# RS_485_V.net
KiCad netlist of a schematic drawn in Altium Designer
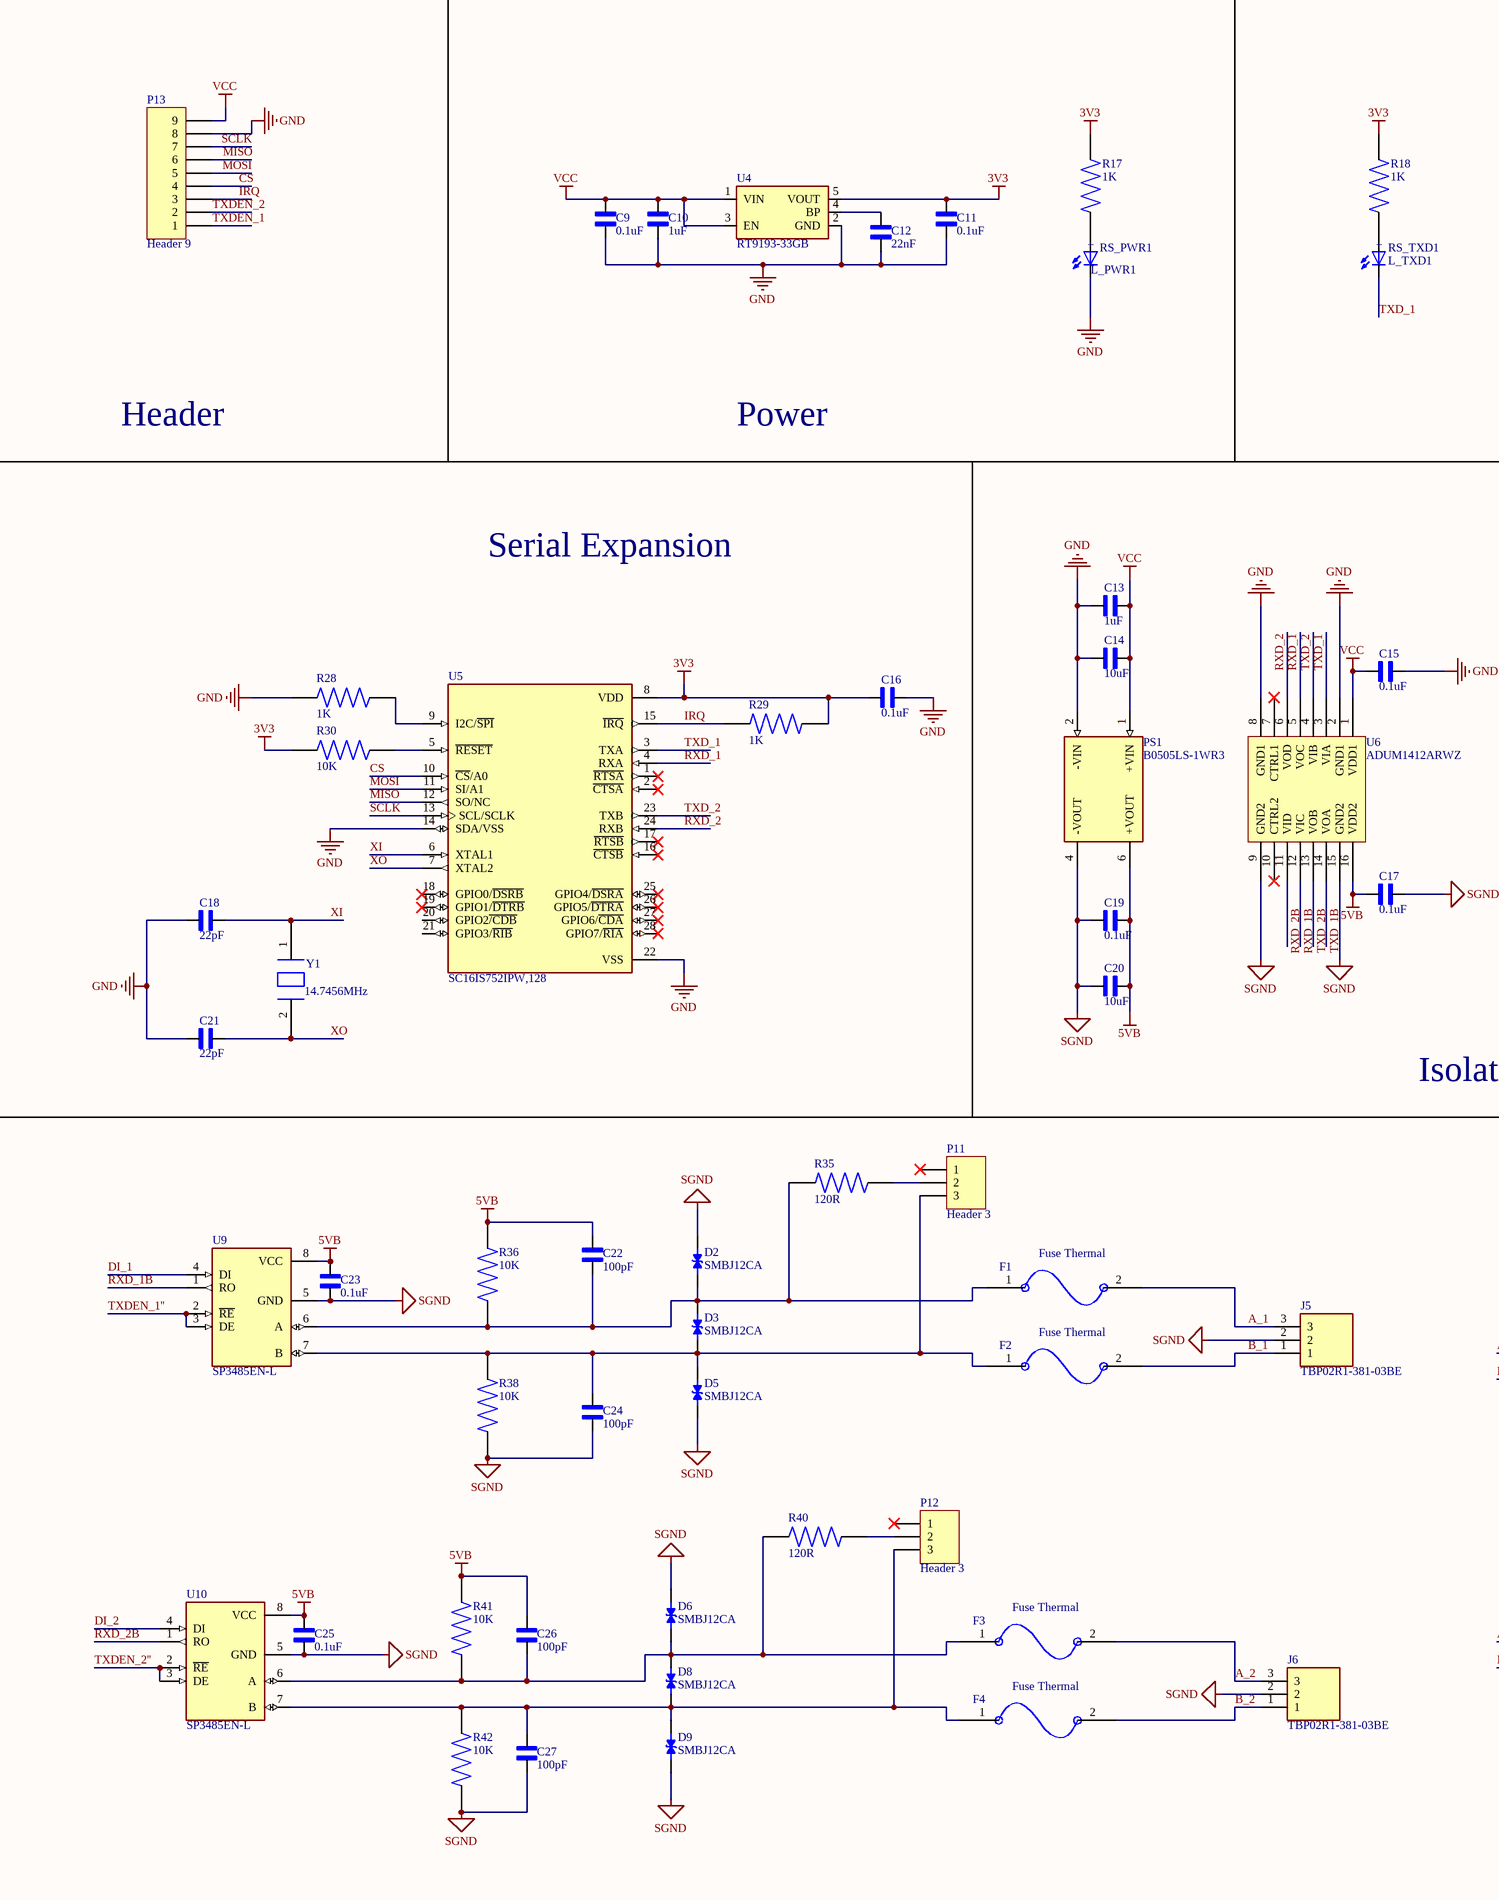
[diagram p0: RS_485_V.SchDoc, left]
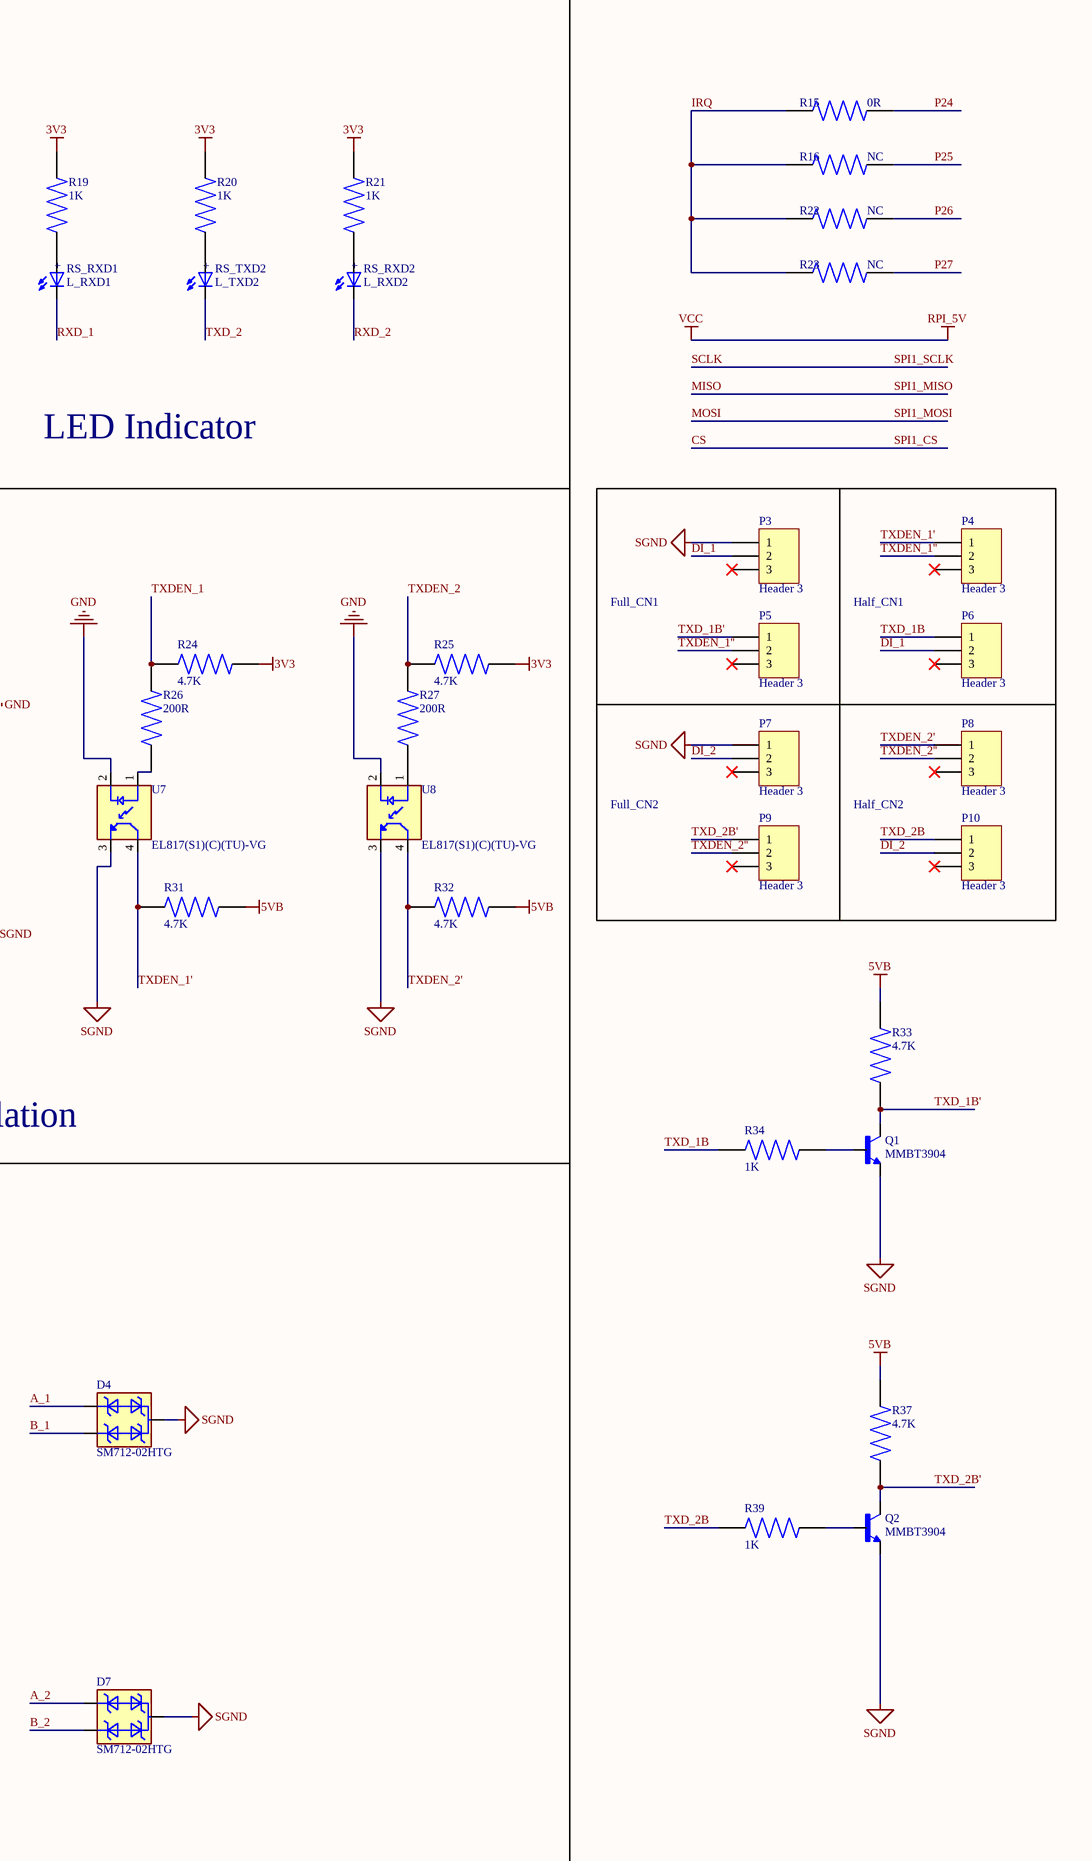
[diagram p1: RS_485_V.SchDoc, right]

(export (version "E")
  (design (tool "Eeschema 10.0.6"))
  (components
    (comp (ref "C9")
      (value "0.1uF")
      (footprint "CAPC1608X94N")
      (description "cap 0603 (1608 Metric)")
      (fields (field (name "MF") "Vishay Vitramon") (field (name "MP") "VJ0603D3R9DXCAP"))
      (libsource (lib "") (part "cap_0603_VJ0603D3R9DXCAP_2"))
    )
    (comp (ref "C10")
      (value "1uF")
      (footprint "CAPC1608X94N")
      (description "cap 0603 (1608 Metric)")
      (fields (field (name "MF") "Vishay Vitramon") (field (name "MP") "VJ0603D3R9DXCAP"))
      (libsource (lib "") (part "cap_0603_VJ0603D3R9DXCAP_2"))
    )
    (comp (ref "C11")
      (value "0.1uF")
      (footprint "CAPC1608X94N")
      (description "cap 0603 (1608 Metric)")
      (fields (field (name "MF") "Vishay Vitramon") (field (name "MP") "VJ0603D3R9DXCAP"))
      (libsource (lib "") (part "cap_0603_VJ0603D3R9DXCAP_2"))
    )
    (comp (ref "C12")
      (value "22nF")
      (footprint "CAPC1608X94N")
      (description "cap 0603 (1608 Metric)")
      (fields (field (name "MF") "Vishay Vitramon") (field (name "MP") "VJ0603D3R9DXCAP"))
      (libsource (lib "") (part "cap_0603_VJ0603D3R9DXCAP_2"))
    )
    (comp (ref "C13")
      (value "1uF")
      (footprint "CAPC1608X94N")
      (description "cap 0603 (1608 Metric)")
      (fields (field (name "MF") "Vishay Vitramon") (field (name "MP") "VJ0603D3R9DXCAP"))
      (libsource (lib "") (part "cap_0603_VJ0603D3R9DXCAP_1"))
    )
    (comp (ref "C14")
      (value "10uF")
      (footprint "CAPC1608X94N")
      (description "cap 0603 (1608 Metric)")
      (fields (field (name "MF") "Vishay Vitramon") (field (name "MP") "VJ0603D3R9DXCAP"))
      (libsource (lib "") (part "cap_0603_VJ0603D3R9DXCAP_1"))
    )
    (comp (ref "C15")
      (value "0.1uF")
      (footprint "CAPC1608X94N")
      (description "cap 0603 (1608 Metric)")
      (fields (field (name "MF") "Vishay Vitramon") (field (name "MP") "VJ0603D3R9DXCAP"))
      (libsource (lib "") (part "cap_0603_VJ0603D3R9DXCAP_1"))
    )
    (comp (ref "C16")
      (value "0.1uF")
      (footprint "CAPC1608X94N")
      (description "cap 0603 (1608 Metric)")
      (fields (field (name "MF") "Vishay Vitramon") (field (name "MP") "VJ0603D3R9DXCAP"))
      (libsource (lib "") (part "cap_0603_VJ0603D3R9DXCAP_1"))
    )
    (comp (ref "C17")
      (value "0.1uF")
      (footprint "CAPC1608X94N")
      (description "cap 0603 (1608 Metric)")
      (fields (field (name "MF") "Vishay Vitramon") (field (name "MP") "VJ0603D3R9DXCAP"))
      (libsource (lib "") (part "cap_0603_VJ0603D3R9DXCAP_1"))
    )
    (comp (ref "C18")
      (value "22pF")
      (footprint "CAPC1608X94N")
      (description "cap 0603 (1608 Metric)")
      (fields (field (name "MF") "Vishay Vitramon") (field (name "MP") "VJ0603D3R9DXCAP"))
      (libsource (lib "") (part "cap_0603_VJ0603D3R9DXCAP_1"))
    )
    (comp (ref "C19")
      (value "0.1uF")
      (footprint "CAPC1608X94N")
      (description "cap 0603 (1608 Metric)")
      (fields (field (name "MF") "Vishay Vitramon") (field (name "MP") "VJ0603D3R9DXCAP"))
      (libsource (lib "") (part "cap_0603_VJ0603D3R9DXCAP_1"))
    )
    (comp (ref "C20")
      (value "10uF")
      (footprint "CAPC1608X94N")
      (description "cap 0603 (1608 Metric)")
      (fields (field (name "MF") "Vishay Vitramon") (field (name "MP") "VJ0603D3R9DXCAP"))
      (libsource (lib "") (part "cap_0603_VJ0603D3R9DXCAP_1"))
    )
    (comp (ref "C21")
      (value "22pF")
      (footprint "CAPC1608X94N")
      (description "cap 0603 (1608 Metric)")
      (fields (field (name "MF") "Vishay Vitramon") (field (name "MP") "VJ0603D3R9DXCAP"))
      (libsource (lib "") (part "cap_0603_VJ0603D3R9DXCAP_1"))
    )
    (comp (ref "C22")
      (value "100pF")
      (footprint "CAPC1608X94N")
      (description "cap 0603 (1608 Metric)")
      (fields (field (name "MF") "Vishay Vitramon") (field (name "MP") "VJ0603D3R9DXCAP"))
      (libsource (lib "VIETTIEN") (part "cap_0603_VJ0603D3R9DXCAP"))
    )
    (comp (ref "C23")
      (value "0.1uF")
      (footprint "CAPC1608X94N")
      (description "cap 0603 (1608 Metric)")
      (fields (field (name "MF") "Vishay Vitramon") (field (name "MP") "VJ0603D3R9DXCAP"))
      (libsource (lib "VIETTIEN") (part "cap_0603_VJ0603D3R9DXCAP"))
    )
    (comp (ref "C24")
      (value "100pF")
      (footprint "CAPC1608X94N")
      (description "cap 0603 (1608 Metric)")
      (fields (field (name "MF") "Vishay Vitramon") (field (name "MP") "VJ0603D3R9DXCAP"))
      (libsource (lib "VIETTIEN") (part "cap_0603_VJ0603D3R9DXCAP"))
    )
    (comp (ref "C25")
      (value "0.1uF")
      (footprint "CAPC1608X94N")
      (description "cap 0603 (1608 Metric)")
      (fields (field (name "MF") "Vishay Vitramon") (field (name "MP") "VJ0603D3R9DXCAP"))
      (libsource (lib "VIETTIEN") (part "cap_0603_VJ0603D3R9DXCAP"))
    )
    (comp (ref "C26")
      (value "100pF")
      (footprint "CAPC1608X94N")
      (description "cap 0603 (1608 Metric)")
      (fields (field (name "MF") "Vishay Vitramon") (field (name "MP") "VJ0603D3R9DXCAP"))
      (libsource (lib "VIETTIEN") (part "cap_0603_VJ0603D3R9DXCAP"))
    )
    (comp (ref "C27")
      (value "100pF")
      (footprint "CAPC1608X94N")
      (description "cap 0603 (1608 Metric)")
      (fields (field (name "MF") "Vishay Vitramon") (field (name "MP") "VJ0603D3R9DXCAP"))
      (libsource (lib "VIETTIEN") (part "cap_0603_VJ0603D3R9DXCAP"))
    )
    (comp (ref "D2")
      (value "SMBJ12CA")
      (footprint "DIOM4336X265N")
      (fields
        (field (name "MF") "{'manufacturer': u'Diodes Incorporated'}")
        (field (name "MP") "SMBJ10CA-13-F")
      )
      (libsource (lib "VIETTIEN") (part "SMBJ10CA-13-F"))
    )
    (comp (ref "D3")
      (value "SMBJ12CA")
      (footprint "DIOM4336X265N")
      (fields
        (field (name "MF") "{'manufacturer': u'Diodes Incorporated'}")
        (field (name "MP") "SMBJ10CA-13-F")
      )
      (libsource (lib "VIETTIEN") (part "SMBJ10CA-13-F"))
    )
    (comp (ref "D4")
      (value "SM712-02HTG")
      (footprint "SOT23")
      (fields (field (name "MF") "Littelfuse Inc."))
      (libsource (lib "VIETTIEN") (part "SM712-02HTG"))
    )
    (comp (ref "D5")
      (value "SMBJ12CA")
      (footprint "DIOM4336X265N")
      (fields
        (field (name "MF") "{'manufacturer': u'Diodes Incorporated'}")
        (field (name "MP") "SMBJ10CA-13-F")
      )
      (libsource (lib "VIETTIEN") (part "SMBJ10CA-13-F"))
    )
    (comp (ref "D6")
      (value "SMBJ12CA")
      (footprint "DIOM4336X265N")
      (fields
        (field (name "MF") "{'manufacturer': u'Diodes Incorporated'}")
        (field (name "MP") "SMBJ10CA-13-F")
      )
      (libsource (lib "VIETTIEN") (part "SMBJ10CA-13-F"))
    )
    (comp (ref "D7")
      (value "SM712-02HTG")
      (footprint "SOT23")
      (fields (field (name "MF") "Littelfuse Inc."))
      (libsource (lib "VIETTIEN") (part "SM712-02HTG"))
    )
    (comp (ref "D8")
      (value "SMBJ12CA")
      (footprint "DIOM4336X265N")
      (fields
        (field (name "MF") "{'manufacturer': u'Diodes Incorporated'}")
        (field (name "MP") "SMBJ10CA-13-F")
      )
      (libsource (lib "VIETTIEN") (part "SMBJ10CA-13-F"))
    )
    (comp (ref "D9")
      (value "SMBJ12CA")
      (footprint "DIOM4336X265N")
      (fields
        (field (name "MF") "{'manufacturer': u'Diodes Incorporated'}")
        (field (name "MP") "SMBJ10CA-13-F")
      )
      (libsource (lib "VIETTIEN") (part "SMBJ10CA-13-F"))
    )
    (comp (ref "F1")
      (value "Fuse Thermal")
      (footprint "Fuse_thermal")
      (libsource (lib "VIETTIEN") (part "Fuse Thermal"))
    )
    (comp (ref "F2")
      (value "Fuse Thermal")
      (footprint "Fuse_thermal")
      (libsource (lib "VIETTIEN") (part "Fuse Thermal"))
    )
    (comp (ref "F3")
      (value "Fuse Thermal")
      (footprint "Fuse_thermal")
      (libsource (lib "VIETTIEN") (part "Fuse Thermal"))
    )
    (comp (ref "F4")
      (value "Fuse Thermal")
      (footprint "Fuse_thermal")
      (libsource (lib "VIETTIEN") (part "Fuse Thermal"))
    )
    (comp (ref "J5")
      (value "TBP02R1-381-03BE")
      (footprint "CUI_TBP02R1-381-03BE")
      (description "2~24 Poles, Pluggable,Receptacle, Horizontal, 3.81 Pitch, Terminal Block Connector")
      (fields (field (name "MF") "Same Sky"))
      (libsource (lib "VIETTIEN") (part "TBP02R1-381-03BE"))
    )
    (comp (ref "J6")
      (value "TBP02R1-381-03BE")
      (footprint "CUI_TBP02R1-381-03BE")
      (description "2~24 Poles, Pluggable,Receptacle, Horizontal, 3.81 Pitch, Terminal Block Connector")
      (fields (field (name "MF") "Same Sky"))
      (libsource (lib "VIETTIEN") (part "TBP02R1-381-03BE"))
    )
    (comp (ref "P3")
      (value "Header 3")
      (footprint "HDR1X3")
      (description "Header, 3-Pin")
      (fields (field (name "PUBLISHER") "Altium Limited"))
      (libsource (lib "Miscellaneous Connectors") (part "Header 3"))
    )
    (comp (ref "P4")
      (value "Header 3")
      (footprint "HDR1X3")
      (description "Header, 3-Pin")
      (fields (field (name "PUBLISHER") "Altium Limited"))
      (libsource (lib "Miscellaneous Connectors") (part "Header 3"))
    )
    (comp (ref "P5")
      (value "Header 3")
      (footprint "HDR1X3")
      (description "Header, 3-Pin")
      (fields (field (name "PUBLISHER") "Altium Limited"))
      (libsource (lib "Miscellaneous Connectors") (part "Header 3"))
    )
    (comp (ref "P6")
      (value "Header 3")
      (footprint "HDR1X3")
      (description "Header, 3-Pin")
      (fields (field (name "PUBLISHER") "Altium Limited"))
      (libsource (lib "Miscellaneous Connectors") (part "Header 3"))
    )
    (comp (ref "P7")
      (value "Header 3")
      (footprint "HDR1X3")
      (description "Header, 3-Pin")
      (fields (field (name "PUBLISHER") "Altium Limited"))
      (libsource (lib "Miscellaneous Connectors") (part "Header 3"))
    )
    (comp (ref "P8")
      (value "Header 3")
      (footprint "HDR1X3")
      (description "Header, 3-Pin")
      (fields (field (name "PUBLISHER") "Altium Limited"))
      (libsource (lib "Miscellaneous Connectors") (part "Header 3"))
    )
    (comp (ref "P9")
      (value "Header 3")
      (footprint "HDR1X3")
      (description "Header, 3-Pin")
      (fields (field (name "PUBLISHER") "Altium Limited"))
      (libsource (lib "Miscellaneous Connectors") (part "Header 3"))
    )
    (comp (ref "P10")
      (value "Header 3")
      (footprint "HDR1X3")
      (description "Header, 3-Pin")
      (fields (field (name "PUBLISHER") "Altium Limited"))
      (libsource (lib "Miscellaneous Connectors") (part "Header 3"))
    )
    (comp (ref "P11")
      (value "Header 3")
      (footprint "HDR1X3")
      (description "Header, 3-Pin")
      (fields (field (name "PUBLISHER") "Altium Limited"))
      (libsource (lib "Miscellaneous Connectors") (part "Header 3"))
    )
    (comp (ref "P12")
      (value "Header 3")
      (footprint "HDR1X3")
      (description "Header, 3-Pin")
      (fields (field (name "PUBLISHER") "Altium Limited"))
      (libsource (lib "Miscellaneous Connectors") (part "Header 3"))
    )
    (comp (ref "P13")
      (value "Header 9")
      (footprint "HDR1X9")
      (description "Header, 9-Pin")
      (fields (field (name "PUBLISHER") "Altium Limited"))
      (libsource (lib "Miscellaneous Connectors") (part "Header 9"))
    )
    (comp (ref "PS1")
      (value "B0505LS-1WR3")
      (footprint "CONV_RFB-0505S")
      (description "1W DC/DC-Converter 'ECONOLINE' SIP7 1kV unreg")
      (fields (field (name "MF") "Recom Power") (field (name "MP") "RFB-0505S"))
      (libsource (lib "VIETTIEN") (part "B0505LS-1WR3"))
    )
    (comp (ref "Q1")
      (value "MMBT3904")
      (footprint "TRANS_MMBT3904")
      (description "BJT, SOT-23, 40V, 200mA, NPN, 0.35W, 150Â°C")
      (fields (field (name "MF") "Diotec Semiconductor"))
      (libsource (lib "VIETTIEN") (part "MMBT3904"))
    )
    (comp (ref "Q2")
      (value "MMBT3904")
      (footprint "TRANS_MMBT3904")
      (description "BJT, SOT-23, 40V, 200mA, NPN, 0.35W, 150Â°C")
      (fields (field (name "MF") "Diotec Semiconductor"))
      (libsource (lib "VIETTIEN") (part "MMBT3904"))
    )
    (comp (ref "R15")
      (value "0R")
      (footprint "RES_ERJU03J474V")
      (description "0603 Anti-Sulfurated")
      (fields (field (name "MF") "Panasonic") (field (name "MP") "ERJU03J474V"))
      (libsource (lib "VIETTIEN") (part "res_0603_ERJU03J474V"))
    )
    (comp (ref "R16")
      (value "NC")
      (footprint "RES_ERJU03J474V")
      (description "0603 Anti-Sulfurated")
      (fields (field (name "MF") "Panasonic") (field (name "MP") "ERJU03J474V"))
      (libsource (lib "VIETTIEN") (part "res_0603_ERJU03J474V"))
    )
    (comp (ref "R17")
      (value "1K")
      (footprint "RES_ERJU03J474V")
      (description "0603 Anti-Sulfurated")
      (fields (field (name "MF") "Panasonic") (field (name "MP") "ERJU03J474V"))
      (libsource (lib "VIETTIEN") (part "res_0603_ERJU03J474V"))
    )
    (comp (ref "R18")
      (value "1K")
      (footprint "RES_ERJU03J474V")
      (description "0603 Anti-Sulfurated")
      (fields (field (name "MF") "Panasonic") (field (name "MP") "ERJU03J474V"))
      (libsource (lib "VIETTIEN") (part "res_0603_ERJU03J474V"))
    )
    (comp (ref "R19")
      (value "1K")
      (footprint "RES_ERJU03J474V")
      (description "0603 Anti-Sulfurated")
      (fields (field (name "MF") "Panasonic") (field (name "MP") "ERJU03J474V"))
      (libsource (lib "VIETTIEN") (part "res_0603_ERJU03J474V"))
    )
    (comp (ref "R20")
      (value "1K")
      (footprint "RES_ERJU03J474V")
      (description "0603 Anti-Sulfurated")
      (fields (field (name "MF") "Panasonic") (field (name "MP") "ERJU03J474V"))
      (libsource (lib "VIETTIEN") (part "res_0603_ERJU03J474V"))
    )
    (comp (ref "R21")
      (value "1K")
      (footprint "RES_ERJU03J474V")
      (description "0603 Anti-Sulfurated")
      (fields (field (name "MF") "Panasonic") (field (name "MP") "ERJU03J474V"))
      (libsource (lib "VIETTIEN") (part "res_0603_ERJU03J474V"))
    )
    (comp (ref "R22")
      (value "NC")
      (footprint "RES_ERJU03J474V")
      (description "0603 Anti-Sulfurated")
      (fields (field (name "MF") "Panasonic") (field (name "MP") "ERJU03J474V"))
      (libsource (lib "VIETTIEN") (part "res_0603_ERJU03J474V"))
    )
    (comp (ref "R23")
      (value "NC")
      (footprint "RES_ERJU03J474V")
      (description "0603 Anti-Sulfurated")
      (fields (field (name "MF") "Panasonic") (field (name "MP") "ERJU03J474V"))
      (libsource (lib "VIETTIEN") (part "res_0603_ERJU03J474V"))
    )
    (comp (ref "R24")
      (value "4.7K")
      (footprint "RES_ERJU03J474V")
      (description "0603 Anti-Sulfurated")
      (fields (field (name "MF") "Panasonic") (field (name "MP") "ERJU03J474V"))
      (libsource (lib "VIETTIEN") (part "res_0603_ERJU03J474V"))
    )
    (comp (ref "R25")
      (value "4.7K")
      (footprint "RES_ERJU03J474V")
      (description "0603 Anti-Sulfurated")
      (fields (field (name "MF") "Panasonic") (field (name "MP") "ERJU03J474V"))
      (libsource (lib "VIETTIEN") (part "res_0603_ERJU03J474V"))
    )
    (comp (ref "R26")
      (value "200R")
      (footprint "RES_ERJU03J474V")
      (description "0603 Anti-Sulfurated")
      (fields (field (name "MF") "Panasonic") (field (name "MP") "ERJU03J474V"))
      (libsource (lib "VIETTIEN") (part "res_0603_ERJU03J474V"))
    )
    (comp (ref "R27")
      (value "200R")
      (footprint "RES_ERJU03J474V")
      (description "0603 Anti-Sulfurated")
      (fields (field (name "MF") "Panasonic") (field (name "MP") "ERJU03J474V"))
      (libsource (lib "VIETTIEN") (part "res_0603_ERJU03J474V"))
    )
    (comp (ref "R28")
      (value "1K")
      (footprint "RES_ERJU03J474V")
      (description "0603 Anti-Sulfurated")
      (fields (field (name "MF") "Panasonic") (field (name "MP") "ERJU03J474V"))
      (libsource (lib "VIETTIEN") (part "res_0603_ERJU03J474V"))
    )
    (comp (ref "R29")
      (value "1K")
      (footprint "RES_ERJU03J474V")
      (description "0603 Anti-Sulfurated")
      (fields (field (name "MF") "Panasonic") (field (name "MP") "ERJU03J474V"))
      (libsource (lib "VIETTIEN") (part "res_0603_ERJU03J474V"))
    )
    (comp (ref "R30")
      (value "10K")
      (footprint "RES_ERJU03J474V")
      (description "0603 Anti-Sulfurated")
      (fields (field (name "MF") "Panasonic") (field (name "MP") "ERJU03J474V"))
      (libsource (lib "VIETTIEN") (part "res_0603_ERJU03J474V"))
    )
    (comp (ref "R31")
      (value "4.7K")
      (footprint "RES_ERJU03J474V")
      (description "0603 Anti-Sulfurated")
      (fields (field (name "MF") "Panasonic") (field (name "MP") "ERJU03J474V"))
      (libsource (lib "VIETTIEN") (part "res_0603_ERJU03J474V"))
    )
    (comp (ref "R32")
      (value "4.7K")
      (footprint "RES_ERJU03J474V")
      (description "0603 Anti-Sulfurated")
      (fields (field (name "MF") "Panasonic") (field (name "MP") "ERJU03J474V"))
      (libsource (lib "VIETTIEN") (part "res_0603_ERJU03J474V"))
    )
    (comp (ref "R33")
      (value "4.7K")
      (footprint "RES_ERJU03J474V")
      (description "0603 Anti-Sulfurated")
      (fields (field (name "MF") "Panasonic") (field (name "MP") "ERJU03J474V"))
      (libsource (lib "VIETTIEN") (part "res_0603_ERJU03J474V"))
    )
    (comp (ref "R34")
      (value "1K")
      (footprint "RES_ERJU03J474V")
      (description "0603 Anti-Sulfurated")
      (fields (field (name "MF") "Panasonic") (field (name "MP") "ERJU03J474V"))
      (libsource (lib "VIETTIEN") (part "res_0603_ERJU03J474V"))
    )
    (comp (ref "R35")
      (value "120R")
      (footprint "RES_ERJU03J474V")
      (description "0603 Anti-Sulfurated")
      (fields (field (name "MF") "Panasonic") (field (name "MP") "ERJU03J474V"))
      (libsource (lib "VIETTIEN") (part "res_0603_ERJU03J474V"))
    )
    (comp (ref "R36")
      (value "10K")
      (footprint "RES_ERJU03J474V")
      (description "0603 Anti-Sulfurated")
      (fields (field (name "MF") "Panasonic") (field (name "MP") "ERJU03J474V"))
      (libsource (lib "VIETTIEN") (part "res_0603_ERJU03J474V"))
    )
    (comp (ref "R37")
      (value "4.7K")
      (footprint "RES_ERJU03J474V")
      (description "0603 Anti-Sulfurated")
      (fields (field (name "MF") "Panasonic") (field (name "MP") "ERJU03J474V"))
      (libsource (lib "VIETTIEN") (part "res_0603_ERJU03J474V"))
    )
    (comp (ref "R38")
      (value "10K")
      (footprint "RES_ERJU03J474V")
      (description "0603 Anti-Sulfurated")
      (fields (field (name "MF") "Panasonic") (field (name "MP") "ERJU03J474V"))
      (libsource (lib "VIETTIEN") (part "res_0603_ERJU03J474V"))
    )
    (comp (ref "R39")
      (value "1K")
      (footprint "RES_ERJU03J474V")
      (description "0603 Anti-Sulfurated")
      (fields (field (name "MF") "Panasonic") (field (name "MP") "ERJU03J474V"))
      (libsource (lib "VIETTIEN") (part "res_0603_ERJU03J474V"))
    )
    (comp (ref "R40")
      (value "120R")
      (footprint "RES_ERJU03J474V")
      (description "0603 Anti-Sulfurated")
      (fields (field (name "MF") "Panasonic") (field (name "MP") "ERJU03J474V"))
      (libsource (lib "VIETTIEN") (part "res_0603_ERJU03J474V"))
    )
    (comp (ref "R41")
      (value "10K")
      (footprint "RES_ERJU03J474V")
      (description "0603 Anti-Sulfurated")
      (fields (field (name "MF") "Panasonic") (field (name "MP") "ERJU03J474V"))
      (libsource (lib "VIETTIEN") (part "res_0603_ERJU03J474V"))
    )
    (comp (ref "R42")
      (value "10K")
      (footprint "RES_ERJU03J474V")
      (description "0603 Anti-Sulfurated")
      (fields (field (name "MF") "Panasonic") (field (name "MP") "ERJU03J474V"))
      (libsource (lib "VIETTIEN") (part "res_0603_ERJU03J474V"))
    )
    (comp (ref "RS_PWR1")
      (value "L_PWR1")
      (footprint "WL-SMCW_1206")
      (description "1206, Blue Typ.(@20mA): 470nm, 145mcd, 3.2V, 140Â° InGaN")
      (fields (field (name "MF") "Wurth Electronics") (field (name "MP") "150120BS75000"))
      (libsource (lib "VIETTIEN") (part "WL-SMCW_1206"))
    )
    (comp (ref "RS_RXD1")
      (value "L_RXD1")
      (footprint "WL-SMCW_1206")
      (description "1206, Blue Typ.(@20mA): 470nm, 145mcd, 3.2V, 140Â° InGaN")
      (fields (field (name "MF") "Wurth Electronics") (field (name "MP") "150120BS75000"))
      (libsource (lib "VIETTIEN") (part "WL-SMCW_1206"))
    )
    (comp (ref "RS_RXD2")
      (value "L_RXD2")
      (footprint "WL-SMCW_1206")
      (description "1206, Blue Typ.(@20mA): 470nm, 145mcd, 3.2V, 140Â° InGaN")
      (fields (field (name "MF") "Wurth Electronics") (field (name "MP") "150120BS75000"))
      (libsource (lib "VIETTIEN") (part "WL-SMCW_1206"))
    )
    (comp (ref "RS_TXD1")
      (value "L_TXD1")
      (footprint "WL-SMCW_1206")
      (description "1206, Blue Typ.(@20mA): 470nm, 145mcd, 3.2V, 140Â° InGaN")
      (fields (field (name "MF") "Wurth Electronics") (field (name "MP") "150120BS75000"))
      (libsource (lib "VIETTIEN") (part "WL-SMCW_1206"))
    )
    (comp (ref "RS_TXD2")
      (value "L_TXD2")
      (footprint "WL-SMCW_1206")
      (description "1206, Blue Typ.(@20mA): 470nm, 145mcd, 3.2V, 140Â° InGaN")
      (fields (field (name "MF") "Wurth Electronics") (field (name "MP") "150120BS75000"))
      (libsource (lib "VIETTIEN") (part "WL-SMCW_1206"))
    )
    (comp (ref "U4")
      (value "RT9193-33GB")
      (footprint "SOT23-5_TEXAS_INSTRUMETNS")
      (description "Linear Voltage Regulator IC Positive Fixed 1 Output  300mA SOT-23-5")
      (fields (field (name "MF") "Richtek Technology Corp") (field (name "MP") "RT919333GB"))
      (libsource (lib "VIETTIEN") (part "RT9193-33GB"))
    )
    (comp (ref "U5")
      (value "SC16IS752IPW,128")
      (footprint "SOP65P640X110-28N")
      (description "RS232, RS485 Controller - IÂ²C, SPI, UART Interface 28-TSSOP")
      (fields (field (name "MF") "NXP Semiconductors"))
      (libsource (lib "VIETTIEN") (part "SC16IS752IPW,128"))
    )
    (comp (ref "U6")
      (value "ADUM1412ARWZ")
      (footprint "SOIC127P1032X265-16N")
      (description "Quad-Channel Digital Isolator")
      (libsource (lib "VIETTIEN") (part "ADUM1412ARWZ"))
    )
    (comp (ref "U7")
      (value "EL817(S1)(C)(TU)-VG")
      (footprint "SOIC254P1030X390-4N_EL817(S1)(C)(TU)-VG")
      (description "Optoisolator Transistor Output 5000Vrms 1 Channel 4-SMD")
      (fields (field (name "MF") "Everlight Electronics") (field (name "MP") "EL817(S1)(A)(TU)-VG"))
      (libsource (lib "VIETTIEN") (part "EL817(S1)(C)(TU)-VG"))
    )
    (comp (ref "U8")
      (value "EL817(S1)(C)(TU)-VG")
      (footprint "SOIC254P1030X390-4N_EL817(S1)(C)(TU)-VG")
      (description "Optoisolator Transistor Output 5000Vrms 1 Channel 4-SMD")
      (fields (field (name "MF") "Everlight Electronics") (field (name "MP") "EL817(S1)(A)(TU)-VG"))
      (libsource (lib "VIETTIEN") (part "EL817(S1)(C)(TU)-VG"))
    )
    (comp (ref "U9")
      (value "SP3485EN-L")
      (footprint "SOIC127P599X175-8N")
      (description "1/1 Transceiver Half RS422, RS485 8-SOIC")
      (fields (field (name "MF") "MaxLinear, Inc."))
      (libsource (lib "VIETTIEN") (part "SP3485EN-L"))
    )
    (comp (ref "U10")
      (value "SP3485EN-L")
      (footprint "SOIC127P599X175-8N")
      (description "1/1 Transceiver Half RS422, RS485 8-SOIC")
      (fields (field (name "MF") "MaxLinear, Inc."))
      (libsource (lib "VIETTIEN") (part "SP3485EN-L"))
    )
    (comp (ref "Y1")
      (value "14.7456MHz")
      (footprint "CRY_HC_49_S")
      (description "Crystal For all Crystal 2pin.")
      (libsource (lib "VIETTIEN") (part "Thach anh"))
    )
  )
  (nets
    (net (code "1") (name "/A_1") (class "Default")
      (node (ref "D4") (pin "1") (pinfunction "1_1") (pintype "passive"))
      (node (ref "F1") (pin "2") (pintype "passive"))
      (node (ref "J5") (pin "3") (pinfunction "3_3") (pintype "passive"))
    )
    (net (code "2") (name "/A_2") (class "Default")
      (node (ref "D7") (pin "1") (pinfunction "1_1") (pintype "passive"))
      (node (ref "F3") (pin "2") (pintype "passive"))
      (node (ref "J6") (pin "3") (pinfunction "3_3") (pintype "passive"))
    )
    (net (code "3") (name "/B_1") (class "Default")
      (node (ref "D4") (pin "2") (pinfunction "2_2") (pintype "passive"))
      (node (ref "F2") (pin "2") (pintype "passive"))
      (node (ref "J5") (pin "1") (pinfunction "1_1") (pintype "passive"))
    )
    (net (code "4") (name "/B_2") (class "Default")
      (node (ref "D7") (pin "2") (pinfunction "2_2") (pintype "passive"))
      (node (ref "F4") (pin "2") (pintype "passive"))
      (node (ref "J6") (pin "1") (pinfunction "1_1") (pintype "passive"))
    )
    (net (code "5") (name "/CS") (class "Default")
      (node (ref "P13") (pin "4") (pinfunction "4_4") (pintype "passive"))
      (node (ref "U5") (pin "10") (pinfunction "~{CS}/A0_10") (pintype "input"))
    )
    (net (code "6") (name "/DI_1") (class "Default")
      (node (ref "P3") (pin "2") (pinfunction "2_2") (pintype "passive"))
      (node (ref "P6") (pin "2") (pinfunction "2_2") (pintype "passive"))
      (node (ref "U9") (pin "4") (pinfunction "DI_4") (pintype "input"))
    )
    (net (code "7") (name "/DI_2") (class "Default")
      (node (ref "P10") (pin "2") (pinfunction "2_2") (pintype "passive"))
      (node (ref "P7") (pin "2") (pinfunction "2_2") (pintype "passive"))
      (node (ref "U10") (pin "4") (pinfunction "DI_4") (pintype "input"))
    )
    (net (code "8") (name "/IRQ") (class "Default")
      (node (ref "P13") (pin "3") (pinfunction "3_3") (pintype "passive"))
      (node (ref "R15") (pin "1") (pinfunction "1_1") (pintype "passive"))
      (node (ref "R16") (pin "1") (pinfunction "1_1") (pintype "passive"))
      (node (ref "R22") (pin "1") (pinfunction "1_1") (pintype "passive"))
      (node (ref "R23") (pin "1") (pinfunction "1_1") (pintype "passive"))
      (node (ref "R29") (pin "1") (pinfunction "1_1") (pintype "passive"))
      (node (ref "U5") (pin "15") (pinfunction "~{IRQ}_15") (pintype "output"))
    )
    (net (code "9") (name "/MISO") (class "Default")
      (node (ref "P13") (pin "6") (pinfunction "6_6") (pintype "passive"))
      (node (ref "U5") (pin "12") (pinfunction "SO/NC_12") (pintype "output"))
    )
    (net (code "10") (name "/MOSI") (class "Default")
      (node (ref "P13") (pin "5") (pinfunction "5_5") (pintype "passive"))
      (node (ref "U5") (pin "11") (pinfunction "SI/A1_11") (pintype "input"))
    )
    (net (code "11") (name "/P24") (class "Default")
      (node (ref "R15") (pin "2") (pinfunction "2_2") (pintype "passive"))
    )
    (net (code "12") (name "/P25") (class "Default")
      (node (ref "R16") (pin "2") (pinfunction "2_2") (pintype "passive"))
    )
    (net (code "13") (name "/P26") (class "Default")
      (node (ref "R22") (pin "2") (pinfunction "2_2") (pintype "passive"))
    )
    (net (code "14") (name "/P27") (class "Default")
      (node (ref "R23") (pin "2") (pinfunction "2_2") (pintype "passive"))
    )
    (net (code "15") (name "/RXD_1") (class "Default")
      (node (ref "RS_RXD1") (pin "1") (pinfunction "NEG_1") (pintype "passive"))
      (node (ref "U5") (pin "4") (pinfunction "RXA_4") (pintype "input"))
      (node (ref "U6") (pin "5") (pinfunction "VOC_5") (pintype "passive"))
    )
    (net (code "16") (name "/RXD_1B") (class "Default")
      (node (ref "U6") (pin "12") (pinfunction "VIC_12") (pintype "passive"))
      (node (ref "U9") (pin "1") (pinfunction "RO_1") (pintype "output"))
    )
    (net (code "17") (name "/RXD_2") (class "Default")
      (node (ref "RS_RXD2") (pin "1") (pinfunction "NEG_1") (pintype "passive"))
      (node (ref "U5") (pin "24") (pinfunction "RXB_24") (pintype "input"))
      (node (ref "U6") (pin "6") (pinfunction "VOD_6") (pintype "passive"))
    )
    (net (code "18") (name "/RXD_2B") (class "Default")
      (node (ref "U10") (pin "1") (pinfunction "RO_1") (pintype "output"))
      (node (ref "U6") (pin "11") (pinfunction "VID_11") (pintype "passive"))
    )
    (net (code "19") (name "/SCLK") (class "Default")
      (node (ref "P13") (pin "7") (pinfunction "7_7") (pintype "passive"))
      (node (ref "U5") (pin "13") (pinfunction "SCL/SCLK_13") (pintype "input"))
    )
    (net (code "20") (name "/TXDEN_1") (class "Default")
      (node (ref "P13") (pin "1") (pinfunction "1_1") (pintype "passive"))
      (node (ref "R24") (pin "2") (pinfunction "2_2") (pintype "passive"))
      (node (ref "R26") (pin "2") (pinfunction "2_2") (pintype "passive"))
    )
    (net (code "21") (name "/TXDEN_1'") (class "Default")
      (node (ref "P4") (pin "1") (pinfunction "1_1") (pintype "passive"))
      (node (ref "R31") (pin "2") (pinfunction "2_2") (pintype "passive"))
      (node (ref "U7") (pin "4") (pinfunction "CT_4") (pintype "passive"))
    )
    (net (code "22") (name "/TXDEN_1''") (class "Default")
      (node (ref "P4") (pin "2") (pinfunction "2_2") (pintype "passive"))
      (node (ref "P5") (pin "2") (pinfunction "2_2") (pintype "passive"))
      (node (ref "U9") (pin "2") (pinfunction "~{RE}_2") (pintype "input"))
      (node (ref "U9") (pin "3") (pinfunction "DE_3") (pintype "input"))
    )
    (net (code "23") (name "/TXDEN_2") (class "Default")
      (node (ref "P13") (pin "2") (pinfunction "2_2") (pintype "passive"))
      (node (ref "R25") (pin "2") (pinfunction "2_2") (pintype "passive"))
      (node (ref "R27") (pin "2") (pinfunction "2_2") (pintype "passive"))
    )
    (net (code "24") (name "/TXDEN_2'") (class "Default")
      (node (ref "P8") (pin "1") (pinfunction "1_1") (pintype "passive"))
      (node (ref "R32") (pin "2") (pinfunction "2_2") (pintype "passive"))
      (node (ref "U8") (pin "4") (pinfunction "CT_4") (pintype "passive"))
    )
    (net (code "25") (name "/TXDEN_2''") (class "Default")
      (node (ref "P8") (pin "2") (pinfunction "2_2") (pintype "passive"))
      (node (ref "P9") (pin "2") (pinfunction "2_2") (pintype "passive"))
      (node (ref "U10") (pin "2") (pinfunction "~{RE}_2") (pintype "input"))
      (node (ref "U10") (pin "3") (pinfunction "DE_3") (pintype "input"))
    )
    (net (code "26") (name "/TXD_1") (class "Default")
      (node (ref "RS_TXD1") (pin "1") (pinfunction "NEG_1") (pintype "passive"))
      (node (ref "U5") (pin "3") (pinfunction "TXA_3") (pintype "output"))
      (node (ref "U6") (pin "3") (pinfunction "VIA_3") (pintype "passive"))
    )
    (net (code "27") (name "/TXD_1B") (class "Default")
      (node (ref "P6") (pin "1") (pinfunction "1_1") (pintype "passive"))
      (node (ref "R34") (pin "1") (pinfunction "1_1") (pintype "passive"))
      (node (ref "U6") (pin "14") (pinfunction "VOA_14") (pintype "passive"))
    )
    (net (code "28") (name "/TXD_1B'") (class "Default")
      (node (ref "P5") (pin "1") (pinfunction "1_1") (pintype "passive"))
      (node (ref "Q1") (pin "3") (pinfunction "C_3") (pintype "passive"))
      (node (ref "R33") (pin "1") (pinfunction "1_1") (pintype "passive"))
    )
    (net (code "29") (name "/TXD_2") (class "Default")
      (node (ref "RS_TXD2") (pin "1") (pinfunction "NEG_1") (pintype "passive"))
      (node (ref "U5") (pin "23") (pinfunction "TXB_23") (pintype "output"))
      (node (ref "U6") (pin "4") (pinfunction "VIB_4") (pintype "passive"))
    )
    (net (code "30") (name "/TXD_2B") (class "Default")
      (node (ref "P10") (pin "1") (pinfunction "1_1") (pintype "passive"))
      (node (ref "R39") (pin "1") (pinfunction "1_1") (pintype "passive"))
      (node (ref "U6") (pin "13") (pinfunction "VOB_13") (pintype "passive"))
    )
    (net (code "31") (name "/TXD_2B'") (class "Default")
      (node (ref "P9") (pin "1") (pinfunction "1_1") (pintype "passive"))
      (node (ref "Q2") (pin "3") (pinfunction "C_3") (pintype "passive"))
      (node (ref "R37") (pin "1") (pinfunction "1_1") (pintype "passive"))
    )
    (net (code "32") (name "/XI") (class "Default")
      (node (ref "C18") (pin "2") (pinfunction "2_2") (pintype "passive"))
      (node (ref "U5") (pin "6") (pinfunction "XTAL1_6") (pintype "input"))
      (node (ref "Y1") (pin "1") (pintype "passive"))
    )
    (net (code "33") (name "/XO") (class "Default")
      (node (ref "C21") (pin "2") (pinfunction "2_2") (pintype "passive"))
      (node (ref "U5") (pin "7") (pinfunction "XTAL2_7") (pintype "output"))
      (node (ref "Y1") (pin "2") (pintype "passive"))
    )
    (net (code "34") (name "3V3") (class "Default")
      (node (ref "C11") (pin "2") (pinfunction "2_2") (pintype "passive"))
      (node (ref "C16") (pin "1") (pinfunction "1_1") (pintype "passive"))
      (node (ref "R17") (pin "2") (pinfunction "2_2") (pintype "passive"))
      (node (ref "R18") (pin "2") (pinfunction "2_2") (pintype "passive"))
      (node (ref "R19") (pin "2") (pinfunction "2_2") (pintype "passive"))
      (node (ref "R20") (pin "2") (pinfunction "2_2") (pintype "passive"))
      (node (ref "R21") (pin "2") (pinfunction "2_2") (pintype "passive"))
      (node (ref "R24") (pin "1") (pinfunction "1_1") (pintype "passive"))
      (node (ref "R25") (pin "1") (pinfunction "1_1") (pintype "passive"))
      (node (ref "R29") (pin "2") (pinfunction "2_2") (pintype "passive"))
      (node (ref "R30") (pin "1") (pinfunction "1_1") (pintype "passive"))
      (node (ref "U4") (pin "5") (pinfunction "VOUT_5") (pintype "bidirectional"))
      (node (ref "U5") (pin "8") (pinfunction "VDD_8") (pintype "power_in"))
    )
    (net (code "35") (name "5VB") (class "Default")
      (node (ref "C17") (pin "1") (pinfunction "1_1") (pintype "passive"))
      (node (ref "C19") (pin "2") (pinfunction "2_2") (pintype "passive"))
      (node (ref "C20") (pin "2") (pinfunction "2_2") (pintype "passive"))
      (node (ref "C22") (pin "1") (pinfunction "1_1") (pintype "passive"))
      (node (ref "C23") (pin "1") (pinfunction "1_1") (pintype "passive"))
      (node (ref "C25") (pin "1") (pinfunction "1_1") (pintype "passive"))
      (node (ref "C26") (pin "1") (pinfunction "1_1") (pintype "passive"))
      (node (ref "PS1") (pin "6") (pinfunction "+VOUT_6") (pintype "power_in"))
      (node (ref "R31") (pin "1") (pinfunction "1_1") (pintype "passive"))
      (node (ref "R32") (pin "1") (pinfunction "1_1") (pintype "passive"))
      (node (ref "R33") (pin "2") (pinfunction "2_2") (pintype "passive"))
      (node (ref "R36") (pin "1") (pinfunction "1_1") (pintype "passive"))
      (node (ref "R37") (pin "2") (pinfunction "2_2") (pintype "passive"))
      (node (ref "R41") (pin "1") (pinfunction "1_1") (pintype "passive"))
      (node (ref "U10") (pin "8") (pinfunction "VCC_8") (pintype "power_in"))
      (node (ref "U6") (pin "16") (pinfunction "VDD2_16") (pintype "passive"))
      (node (ref "U9") (pin "8") (pinfunction "VCC_8") (pintype "power_in"))
    )
    (net (code "36") (name "GND") (class "Default")
      (node (ref "C10") (pin "1") (pinfunction "1_1") (pintype "passive"))
      (node (ref "C11") (pin "1") (pinfunction "1_1") (pintype "passive"))
      (node (ref "C12") (pin "1") (pinfunction "1_1") (pintype "passive"))
      (node (ref "C13") (pin "1") (pinfunction "1_1") (pintype "passive"))
      (node (ref "C14") (pin "1") (pinfunction "1_1") (pintype "passive"))
      (node (ref "C15") (pin "2") (pinfunction "2_2") (pintype "passive"))
      (node (ref "C16") (pin "2") (pinfunction "2_2") (pintype "passive"))
      (node (ref "C18") (pin "1") (pinfunction "1_1") (pintype "passive"))
      (node (ref "C21") (pin "1") (pinfunction "1_1") (pintype "passive"))
      (node (ref "C9") (pin "1") (pinfunction "1_1") (pintype "passive"))
      (node (ref "P13") (pin "8") (pinfunction "8_8") (pintype "passive"))
      (node (ref "PS1") (pin "2") (pinfunction "-VIN_2") (pintype "input"))
      (node (ref "R28") (pin "1") (pinfunction "1_1") (pintype "passive"))
      (node (ref "RS_PWR1") (pin "1") (pinfunction "NEG_1") (pintype "passive"))
      (node (ref "U4") (pin "2") (pinfunction "GND_2") (pintype "bidirectional"))
      (node (ref "U5") (pin "14") (pinfunction "SDA/VSS_14") (pintype "bidirectional"))
      (node (ref "U5") (pin "22") (pinfunction "VSS_22") (pintype "power_in"))
      (node (ref "U6") (pin "2") (pinfunction "GND1_2") (pintype "passive"))
      (node (ref "U6") (pin "8") (pinfunction "GND1_8") (pintype "passive"))
      (node (ref "U7") (pin "2") (pinfunction "C_2") (pintype "passive"))
      (node (ref "U8") (pin "2") (pinfunction "C_2") (pintype "passive"))
    )
    (net (code "37") (name "Net-(P11-Pad2)") (class "Default")
      (node (ref "P11") (pin "2") (pinfunction "2_2") (pintype "passive"))
      (node (ref "R35") (pin "2") (pinfunction "2_2") (pintype "passive"))
    )
    (net (code "38") (name "Net-(P12-Pad2)") (class "Default")
      (node (ref "P12") (pin "2") (pinfunction "2_2") (pintype "passive"))
      (node (ref "R40") (pin "2") (pinfunction "2_2") (pintype "passive"))
    )
    (net (code "39") (name "Net-(Q1-B)") (class "Default")
      (node (ref "Q1") (pin "1") (pinfunction "B_1") (pintype "passive"))
      (node (ref "R34") (pin "2") (pinfunction "2_2") (pintype "passive"))
    )
    (net (code "40") (name "Net-(Q2-B)") (class "Default")
      (node (ref "Q2") (pin "1") (pinfunction "B_1") (pintype "passive"))
      (node (ref "R39") (pin "2") (pinfunction "2_2") (pintype "passive"))
    )
    (net (code "41") (name "Net-(RS_PWR1-POS)") (class "Default")
      (node (ref "R17") (pin "1") (pinfunction "1_1") (pintype "passive"))
      (node (ref "RS_PWR1") (pin "2") (pinfunction "POS_2") (pintype "passive"))
    )
    (net (code "42") (name "Net-(RS_RXD1-POS)") (class "Default")
      (node (ref "R19") (pin "1") (pinfunction "1_1") (pintype "passive"))
      (node (ref "RS_RXD1") (pin "2") (pinfunction "POS_2") (pintype "passive"))
    )
    (net (code "43") (name "Net-(RS_RXD2-POS)") (class "Default")
      (node (ref "R21") (pin "1") (pinfunction "1_1") (pintype "passive"))
      (node (ref "RS_RXD2") (pin "2") (pinfunction "POS_2") (pintype "passive"))
    )
    (net (code "44") (name "Net-(RS_TXD1-POS)") (class "Default")
      (node (ref "R18") (pin "1") (pinfunction "1_1") (pintype "passive"))
      (node (ref "RS_TXD1") (pin "2") (pinfunction "POS_2") (pintype "passive"))
    )
    (net (code "45") (name "Net-(RS_TXD2-POS)") (class "Default")
      (node (ref "R20") (pin "1") (pinfunction "1_1") (pintype "passive"))
      (node (ref "RS_TXD2") (pin "2") (pinfunction "POS_2") (pintype "passive"))
    )
    (net (code "46") (name "Net-(U4-BP)") (class "Default")
      (node (ref "C12") (pin "2") (pinfunction "2_2") (pintype "passive"))
      (node (ref "U4") (pin "4") (pinfunction "BP_4") (pintype "bidirectional"))
    )
    (net (code "47") (name "Net-(U5-I2C{slash}~{SPI})") (class "Default")
      (node (ref "R28") (pin "2") (pinfunction "2_2") (pintype "passive"))
      (node (ref "U5") (pin "9") (pinfunction "I2C/~{SPI}_9") (pintype "input"))
    )
    (net (code "48") (name "Net-(U5-~{RESET})") (class "Default")
      (node (ref "R30") (pin "2") (pinfunction "2_2") (pintype "passive"))
      (node (ref "U5") (pin "5") (pinfunction "~{RESET}_5") (pintype "input"))
    )
    (net (code "49") (name "Net-(U7-A)") (class "Default")
      (node (ref "R26") (pin "1") (pinfunction "1_1") (pintype "passive"))
      (node (ref "U7") (pin "1") (pinfunction "A_1") (pintype "passive"))
    )
    (net (code "50") (name "Net-(U8-A)") (class "Default")
      (node (ref "R27") (pin "1") (pinfunction "1_1") (pintype "passive"))
      (node (ref "U8") (pin "1") (pinfunction "A_1") (pintype "passive"))
    )
    (net (code "51") (name "Net-(U9-A)") (class "Default")
      (node (ref "C22") (pin "2") (pinfunction "2_2") (pintype "passive"))
      (node (ref "D2") (pin "1") (pinfunction "1_1") (pintype "passive"))
      (node (ref "D3") (pin "1") (pinfunction "1_1") (pintype "passive"))
      (node (ref "F1") (pin "1") (pintype "passive"))
      (node (ref "R35") (pin "1") (pinfunction "1_1") (pintype "passive"))
      (node (ref "R36") (pin "2") (pinfunction "2_2") (pintype "passive"))
      (node (ref "U9") (pin "6") (pinfunction "A_6") (pintype "bidirectional"))
    )
    (net (code "52") (name "Net-(U9-B)") (class "Default")
      (node (ref "C24") (pin "1") (pinfunction "1_1") (pintype "passive"))
      (node (ref "D3") (pin "2") (pinfunction "2_2") (pintype "passive"))
      (node (ref "D5") (pin "1") (pinfunction "1_1") (pintype "passive"))
      (node (ref "F2") (pin "1") (pintype "passive"))
      (node (ref "P11") (pin "3") (pinfunction "3_3") (pintype "passive"))
      (node (ref "R38") (pin "1") (pinfunction "1_1") (pintype "passive"))
      (node (ref "U9") (pin "7") (pinfunction "B_7") (pintype "bidirectional"))
    )
    (net (code "53") (name "Net-(U10-A)") (class "Default")
      (node (ref "C26") (pin "2") (pinfunction "2_2") (pintype "passive"))
      (node (ref "D6") (pin "1") (pinfunction "1_1") (pintype "passive"))
      (node (ref "D8") (pin "1") (pinfunction "1_1") (pintype "passive"))
      (node (ref "F3") (pin "1") (pintype "passive"))
      (node (ref "R40") (pin "1") (pinfunction "1_1") (pintype "passive"))
      (node (ref "R41") (pin "2") (pinfunction "2_2") (pintype "passive"))
      (node (ref "U10") (pin "6") (pinfunction "A_6") (pintype "bidirectional"))
    )
    (net (code "54") (name "Net-(U10-B)") (class "Default")
      (node (ref "C27") (pin "1") (pinfunction "1_1") (pintype "passive"))
      (node (ref "D8") (pin "2") (pinfunction "2_2") (pintype "passive"))
      (node (ref "D9") (pin "1") (pinfunction "1_1") (pintype "passive"))
      (node (ref "F4") (pin "1") (pintype "passive"))
      (node (ref "P12") (pin "3") (pinfunction "3_3") (pintype "passive"))
      (node (ref "R42") (pin "1") (pinfunction "1_1") (pintype "passive"))
      (node (ref "U10") (pin "7") (pinfunction "B_7") (pintype "bidirectional"))
    )
    (net (code "55") (name "RPI_5V") (class "Default")
      (node (ref "C10") (pin "2") (pinfunction "2_2") (pintype "passive"))
      (node (ref "C13") (pin "2") (pinfunction "2_2") (pintype "passive"))
      (node (ref "C14") (pin "2") (pinfunction "2_2") (pintype "passive"))
      (node (ref "C15") (pin "1") (pinfunction "1_1") (pintype "passive"))
      (node (ref "C9") (pin "2") (pinfunction "2_2") (pintype "passive"))
      (node (ref "P13") (pin "9") (pinfunction "9_9") (pintype "passive"))
      (node (ref "PS1") (pin "1") (pinfunction "+VIN_1") (pintype "input"))
      (node (ref "U4") (pin "1") (pinfunction "VIN_1") (pintype "bidirectional"))
      (node (ref "U4") (pin "3") (pinfunction "EN_3") (pintype "bidirectional"))
      (node (ref "U6") (pin "1") (pinfunction "VDD1_1") (pintype "passive"))
    )
    (net (code "56") (name "SGND") (class "Default")
      (node (ref "C17") (pin "2") (pinfunction "2_2") (pintype "passive"))
      (node (ref "C19") (pin "1") (pinfunction "1_1") (pintype "passive"))
      (node (ref "C20") (pin "1") (pinfunction "1_1") (pintype "passive"))
      (node (ref "C23") (pin "2") (pinfunction "2_2") (pintype "passive"))
      (node (ref "C24") (pin "2") (pinfunction "2_2") (pintype "passive"))
      (node (ref "C25") (pin "2") (pinfunction "2_2") (pintype "passive"))
      (node (ref "C27") (pin "2") (pinfunction "2_2") (pintype "passive"))
      (node (ref "D2") (pin "2") (pinfunction "2_2") (pintype "passive"))
      (node (ref "D4") (pin "3") (pinfunction "3_3") (pintype "passive"))
      (node (ref "D5") (pin "2") (pinfunction "2_2") (pintype "passive"))
      (node (ref "D6") (pin "2") (pinfunction "2_2") (pintype "passive"))
      (node (ref "D7") (pin "3") (pinfunction "3_3") (pintype "passive"))
      (node (ref "D9") (pin "2") (pinfunction "2_2") (pintype "passive"))
      (node (ref "J5") (pin "2") (pinfunction "2_2") (pintype "passive"))
      (node (ref "J6") (pin "2") (pinfunction "2_2") (pintype "passive"))
      (node (ref "P3") (pin "1") (pinfunction "1_1") (pintype "passive"))
      (node (ref "P7") (pin "1") (pinfunction "1_1") (pintype "passive"))
      (node (ref "PS1") (pin "4") (pinfunction "-VOUT_4") (pintype "passive"))
      (node (ref "Q1") (pin "2") (pinfunction "E_2") (pintype "passive"))
      (node (ref "Q2") (pin "2") (pinfunction "E_2") (pintype "passive"))
      (node (ref "R38") (pin "2") (pinfunction "2_2") (pintype "passive"))
      (node (ref "R42") (pin "2") (pinfunction "2_2") (pintype "passive"))
      (node (ref "U10") (pin "5") (pinfunction "GND_5") (pintype "power_in"))
      (node (ref "U6") (pin "15") (pinfunction "GND2_15") (pintype "passive"))
      (node (ref "U6") (pin "9") (pinfunction "GND2_9") (pintype "passive"))
      (node (ref "U7") (pin "3") (pinfunction "ET_3") (pintype "passive"))
      (node (ref "U8") (pin "3") (pinfunction "ET_3") (pintype "passive"))
      (node (ref "U9") (pin "5") (pinfunction "GND_5") (pintype "power_in"))
    )
    (net (code "57") (name "unconnected-(P3-Pad3)") (class "Default")
      (node (ref "P3") (pin "3") (pinfunction "3_3") (pintype "passive+no_connect"))
    )
    (net (code "58") (name "unconnected-(P4-Pad3)") (class "Default")
      (node (ref "P4") (pin "3") (pinfunction "3_3") (pintype "passive+no_connect"))
    )
    (net (code "59") (name "unconnected-(P5-Pad3)") (class "Default")
      (node (ref "P5") (pin "3") (pinfunction "3_3") (pintype "passive+no_connect"))
    )
    (net (code "60") (name "unconnected-(P6-Pad3)") (class "Default")
      (node (ref "P6") (pin "3") (pinfunction "3_3") (pintype "passive+no_connect"))
    )
    (net (code "61") (name "unconnected-(P7-Pad3)") (class "Default")
      (node (ref "P7") (pin "3") (pinfunction "3_3") (pintype "passive+no_connect"))
    )
    (net (code "62") (name "unconnected-(P8-Pad3)") (class "Default")
      (node (ref "P8") (pin "3") (pinfunction "3_3") (pintype "passive+no_connect"))
    )
    (net (code "63") (name "unconnected-(P9-Pad3)") (class "Default")
      (node (ref "P9") (pin "3") (pinfunction "3_3") (pintype "passive+no_connect"))
    )
    (net (code "64") (name "unconnected-(P10-Pad3)") (class "Default")
      (node (ref "P10") (pin "3") (pinfunction "3_3") (pintype "passive+no_connect"))
    )
    (net (code "65") (name "unconnected-(P11-Pad1)") (class "Default")
      (node (ref "P11") (pin "1") (pinfunction "1_1") (pintype "passive+no_connect"))
    )
    (net (code "66") (name "unconnected-(P12-Pad1)") (class "Default")
      (node (ref "P12") (pin "1") (pinfunction "1_1") (pintype "passive+no_connect"))
    )
    (net (code "67") (name "unconnected-(U5-GPIO0{slash}~{DSRB}-Pad18)") (class "Default")
      (node (ref "U5") (pin "18") (pinfunction "GPIO0/~{DSRB}_18") (pintype "bidirectional+no_connect"))
    )
    (net (code "68") (name "unconnected-(U5-GPIO1{slash}~{DTRB}-Pad19)") (class "Default")
      (node (ref "U5") (pin "19") (pinfunction "GPIO1/~{DTRB}_19") (pintype "bidirectional+no_connect"))
    )
    (net (code "69") (name "unconnected-(U5-GPIO2~{{slash}CDB}-Pad20)") (class "Default")
      (node (ref "U5") (pin "20") (pinfunction "GPIO2~{/CDB}_20") (pintype "bidirectional"))
    )
    (net (code "70") (name "unconnected-(U5-GPIO3{slash}~{RIB}-Pad21)") (class "Default")
      (node (ref "U5") (pin "21") (pinfunction "GPIO3/~{RIB}_21") (pintype "bidirectional"))
    )
    (net (code "71") (name "unconnected-(U5-GPIO4{slash}~{DSRA}-Pad25)") (class "Default")
      (node (ref "U5") (pin "25") (pinfunction "GPIO4/~{DSRA}_25") (pintype "bidirectional+no_connect"))
    )
    (net (code "72") (name "unconnected-(U5-GPIO5{slash}~{DTRA}-Pad26)") (class "Default")
      (node (ref "U5") (pin "26") (pinfunction "GPIO5/~{DTRA}_26") (pintype "bidirectional+no_connect"))
    )
    (net (code "73") (name "unconnected-(U5-GPIO6{slash}~{CDA}-Pad27)") (class "Default")
      (node (ref "U5") (pin "27") (pinfunction "GPIO6/~{CDA}_27") (pintype "bidirectional+no_connect"))
    )
    (net (code "74") (name "unconnected-(U5-GPIO7{slash}~{RIA}-Pad28)") (class "Default")
      (node (ref "U5") (pin "28") (pinfunction "GPIO7/~{RIA}_28") (pintype "bidirectional+no_connect"))
    )
    (net (code "75") (name "unconnected-(U5-~{CTSA}-Pad2)") (class "Default")
      (node (ref "U5") (pin "2") (pinfunction "~{CTSA}_2") (pintype "input+no_connect"))
    )
    (net (code "76") (name "unconnected-(U5-~{CTSB}-Pad16)") (class "Default")
      (node (ref "U5") (pin "16") (pinfunction "~{CTSB}_16") (pintype "input+no_connect"))
    )
    (net (code "77") (name "unconnected-(U5-~{RTSA}-Pad1)") (class "Default")
      (node (ref "U5") (pin "1") (pinfunction "~{RTSA}_1") (pintype "output+no_connect"))
    )
    (net (code "78") (name "unconnected-(U5-~{RTSB}-Pad17)") (class "Default")
      (node (ref "U5") (pin "17") (pinfunction "~{RTSB}_17") (pintype "output+no_connect"))
    )
    (net (code "79") (name "unconnected-(U6-CTRL1-Pad7)") (class "Default")
      (node (ref "U6") (pin "7") (pinfunction "CTRL1_7") (pintype "passive+no_connect"))
    )
    (net (code "80") (name "unconnected-(U6-CTRL2-Pad10)") (class "Default")
      (node (ref "U6") (pin "10") (pinfunction "CTRL2_10") (pintype "passive+no_connect"))
    )
  )
)
